# TOP.net
KiCad netlist of a schematic drawn in Altium Designer
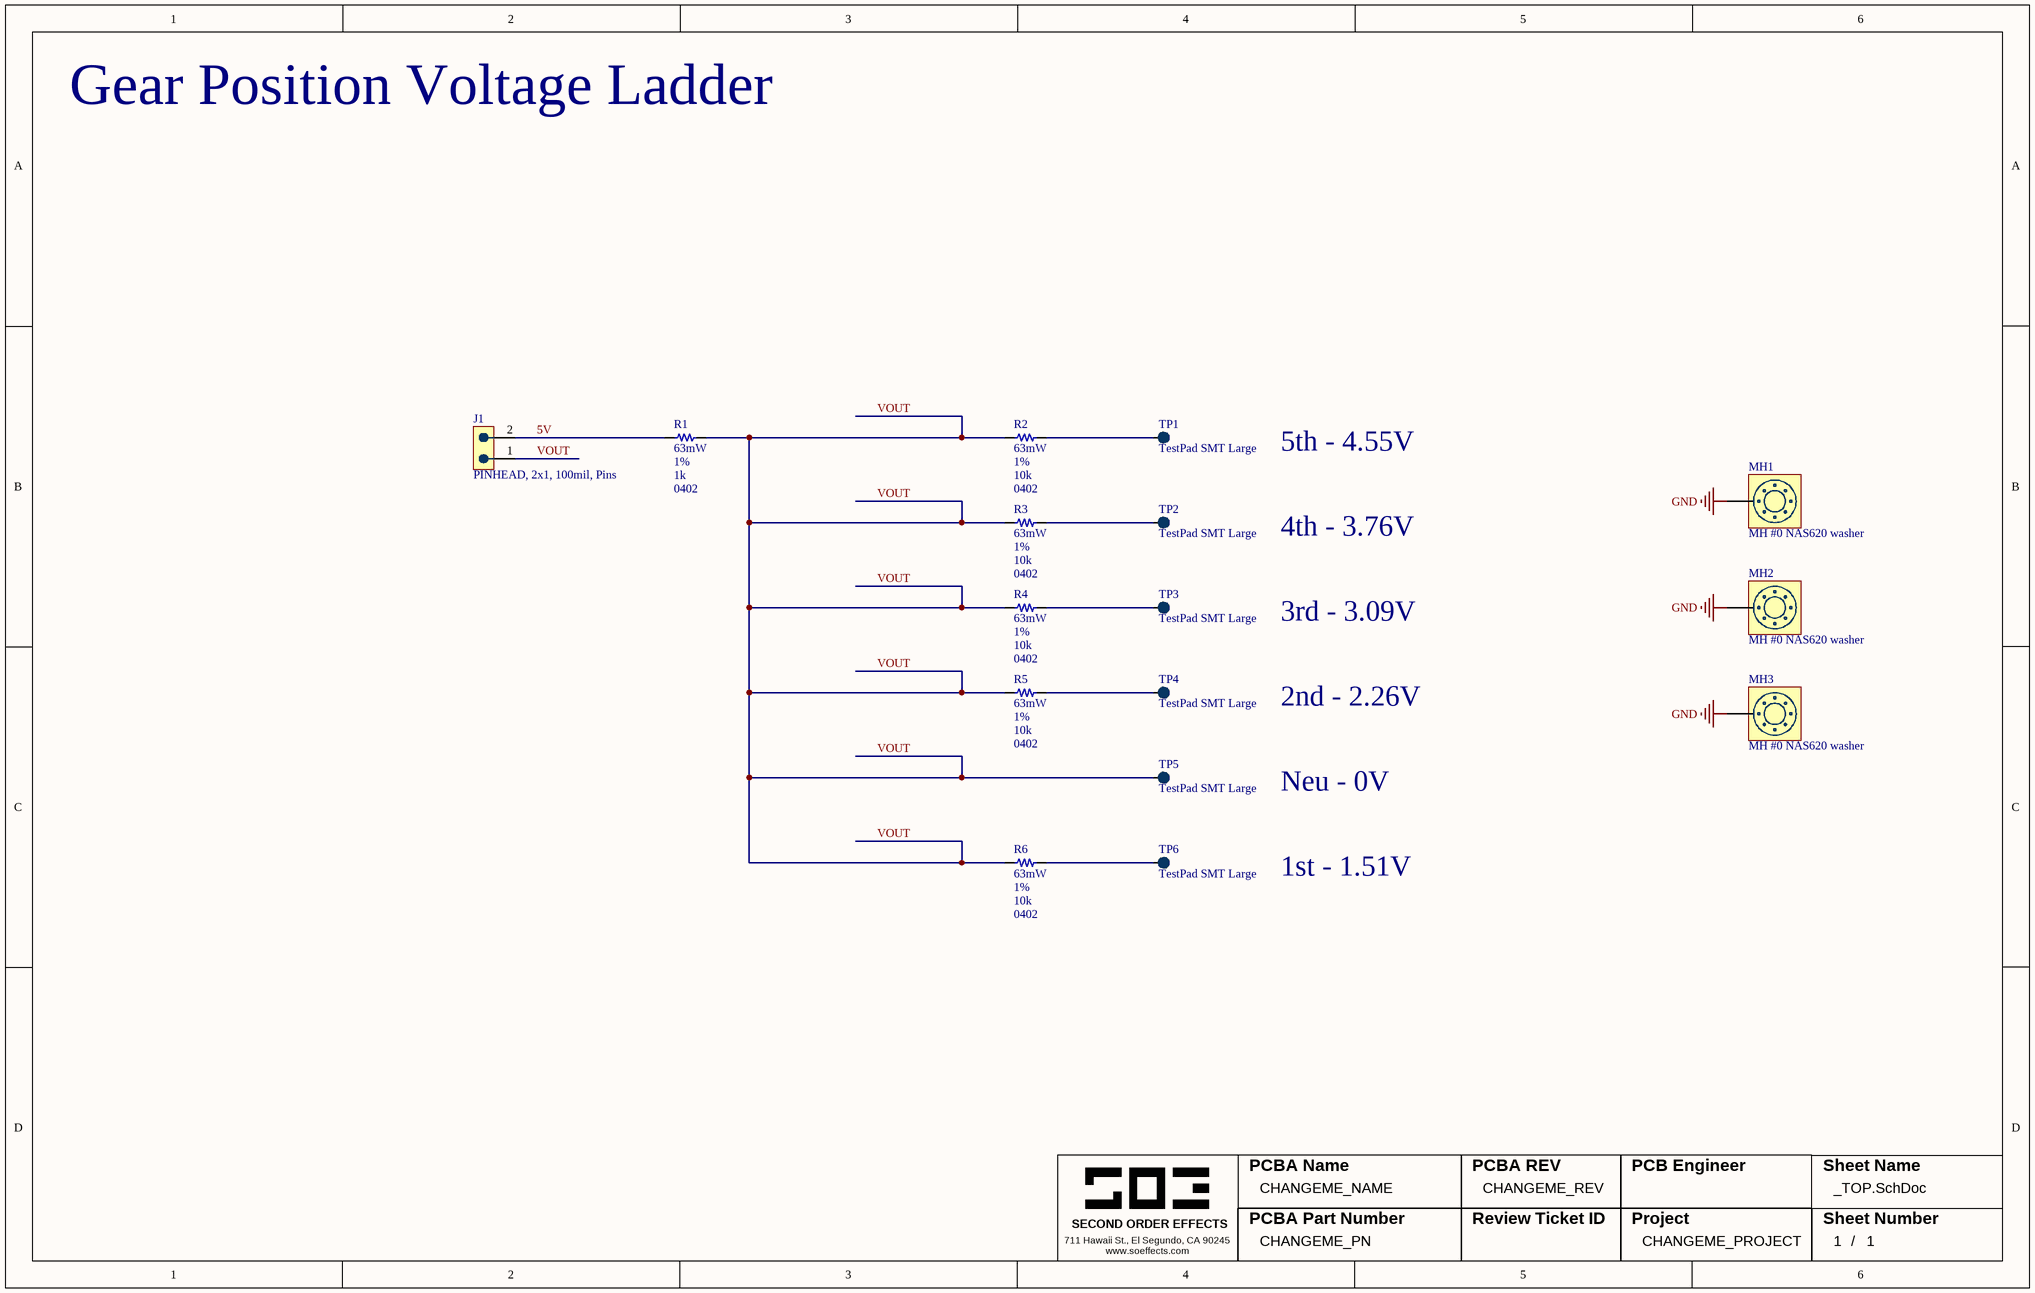
[diagram p0: _TOP.SchDoc]

(export (version "E")
  (design (tool "Eeschema 10.0.6"))
  (components
    (comp (ref "J1")
      (value "PINHEAD, 2x1, 100mil, Pins")
      (footprint "PINHEAD 2 x 1 100MIL PIN")
      (description "Headers & Wire Housings 2.54MM CGRIDIII HDR 2P VERT SR SEL AU")
      (libsource (lib "SOE Vault") (part "PINHEAD 2x1 PINS"))
    )
    (comp (ref "MH1")
      (value "MH #0 NAS620 washer")
      (footprint "MH_0_NAS620")
      (libsource (lib "SOE Vault") (part "MountingHole-4mm"))
    )
    (comp (ref "MH2")
      (value "MH #0 NAS620 washer")
      (footprint "MH_0_NAS620")
      (libsource (lib "SOE Vault") (part "MountingHole-4mm"))
    )
    (comp (ref "MH3")
      (value "MH #0 NAS620 washer")
      (footprint "MH_0_NAS620")
      (libsource (lib "SOE Vault") (part "MountingHole-4mm"))
    )
    (comp (ref "R1")
      (value "R 0402 1.00k 1% 0.063W ±100PPM/°C 50V AEC-Q200")
      (footprint "R_0402")
      (description "SMD Resistor, Thick Film, Automotive")
      (fields
        (field (name "POWER RATING") "63mW")
        (field (name "TOLERANCE") "1%")
        (field (name "RESISTANCE") "1k")
        (field (name "CASE/PACKAGE") "0402")
      )
      (libsource (lib "SOE Vault") (part "r4"))
    )
    (comp (ref "R2")
      (value "R 0402 10.0k 1% 0.063W ±100PPM/°C 50V AEC-Q200")
      (footprint "R_0402")
      (description "SMD Resistor, Thick Film, Automotive")
      (fields
        (field (name "POWER RATING") "63mW")
        (field (name "TOLERANCE") "1%")
        (field (name "RESISTANCE") "10k")
        (field (name "CASE/PACKAGE") "0402")
      )
      (libsource (lib "SOE Vault") (part "r4"))
    )
    (comp (ref "R3")
      (value "R 0402 10.0k 1% 0.063W ±100PPM/°C 50V AEC-Q200")
      (footprint "R_0402")
      (description "SMD Resistor, Thick Film, Automotive")
      (fields
        (field (name "POWER RATING") "63mW")
        (field (name "TOLERANCE") "1%")
        (field (name "RESISTANCE") "10k")
        (field (name "CASE/PACKAGE") "0402")
      )
      (libsource (lib "SOE Vault") (part "r4"))
    )
    (comp (ref "R4")
      (value "R 0402 10.0k 1% 0.063W ±100PPM/°C 50V AEC-Q200")
      (footprint "R_0402")
      (description "SMD Resistor, Thick Film, Automotive")
      (fields
        (field (name "POWER RATING") "63mW")
        (field (name "TOLERANCE") "1%")
        (field (name "RESISTANCE") "10k")
        (field (name "CASE/PACKAGE") "0402")
      )
      (libsource (lib "SOE Vault") (part "r4"))
    )
    (comp (ref "R5")
      (value "R 0402 10.0k 1% 0.063W ±100PPM/°C 50V AEC-Q200")
      (footprint "R_0402")
      (description "SMD Resistor, Thick Film, Automotive")
      (fields
        (field (name "POWER RATING") "63mW")
        (field (name "TOLERANCE") "1%")
        (field (name "RESISTANCE") "10k")
        (field (name "CASE/PACKAGE") "0402")
      )
      (libsource (lib "SOE Vault") (part "r4"))
    )
    (comp (ref "R6")
      (value "R 0402 10.0k 1% 0.063W ±100PPM/°C 50V AEC-Q200")
      (footprint "R_0402")
      (description "SMD Resistor, Thick Film, Automotive")
      (fields
        (field (name "POWER RATING") "63mW")
        (field (name "TOLERANCE") "1%")
        (field (name "RESISTANCE") "10k")
        (field (name "CASE/PACKAGE") "0402")
      )
      (libsource (lib "SOE Vault") (part "r4"))
    )
    (comp (ref "TP1")
      (value "TestPad SMT Large")
      (footprint "TEST_POINT_SMD_LARGE")
      (description "Test pad 2mm")
      (libsource (lib "SOE Vault") (part "TestPad"))
    )
    (comp (ref "TP2")
      (value "TestPad SMT Large")
      (footprint "TEST_POINT_SMD_LARGE")
      (description "Test pad 2mm")
      (libsource (lib "SOE Vault") (part "TestPad"))
    )
    (comp (ref "TP3")
      (value "TestPad SMT Large")
      (footprint "TEST_POINT_SMD_LARGE")
      (description "Test pad 2mm")
      (libsource (lib "SOE Vault") (part "TestPad"))
    )
    (comp (ref "TP4")
      (value "TestPad SMT Large")
      (footprint "TEST_POINT_SMD_LARGE")
      (description "Test pad 2mm")
      (libsource (lib "SOE Vault") (part "TestPad"))
    )
    (comp (ref "TP5")
      (value "TestPad SMT Large")
      (footprint "TEST_POINT_SMD_LARGE")
      (description "Test pad 2mm")
      (libsource (lib "SOE Vault") (part "TestPad"))
    )
    (comp (ref "TP6")
      (value "TestPad SMT Large")
      (footprint "TEST_POINT_SMD_LARGE")
      (description "Test pad 2mm")
      (libsource (lib "SOE Vault") (part "TestPad"))
    )
  )
  (nets
    (net (code "1") (name "/5V") (class "Default")
      (node (ref "J1") (pin "2") (pinfunction "2_2") (pintype "passive"))
      (node (ref "R1") (pin "2") (pinfunction "2_2") (pintype "passive"))
    )
    (net (code "2") (name "/VOUT") (class "Default")
      (node (ref "J1") (pin "1") (pinfunction "1_1") (pintype "passive"))
      (node (ref "R1") (pin "1") (pinfunction "1_1") (pintype "passive"))
      (node (ref "R2") (pin "2") (pinfunction "2_2") (pintype "passive"))
      (node (ref "R3") (pin "2") (pinfunction "2_2") (pintype "passive"))
      (node (ref "R4") (pin "2") (pinfunction "2_2") (pintype "passive"))
      (node (ref "R5") (pin "2") (pinfunction "2_2") (pintype "passive"))
      (node (ref "R6") (pin "2") (pinfunction "2_2") (pintype "passive"))
      (node (ref "TP5") (pin "1") (pinfunction "TP_1") (pintype "passive"))
    )
    (net (code "3") (name "GND") (class "Default")
      (node (ref "MH1") (pin "1") (pinfunction "MH_1") (pintype "passive"))
      (node (ref "MH2") (pin "1") (pinfunction "MH_1") (pintype "passive"))
      (node (ref "MH3") (pin "1") (pinfunction "MH_1") (pintype "passive"))
    )
    (net (code "4") (name "Net-(TP1-TP)") (class "Default")
      (node (ref "R2") (pin "1") (pinfunction "1_1") (pintype "passive"))
      (node (ref "TP1") (pin "1") (pinfunction "TP_1") (pintype "passive"))
    )
    (net (code "5") (name "Net-(TP2-TP)") (class "Default")
      (node (ref "R3") (pin "1") (pinfunction "1_1") (pintype "passive"))
      (node (ref "TP2") (pin "1") (pinfunction "TP_1") (pintype "passive"))
    )
    (net (code "6") (name "Net-(TP3-TP)") (class "Default")
      (node (ref "R4") (pin "1") (pinfunction "1_1") (pintype "passive"))
      (node (ref "TP3") (pin "1") (pinfunction "TP_1") (pintype "passive"))
    )
    (net (code "7") (name "Net-(TP4-TP)") (class "Default")
      (node (ref "R5") (pin "1") (pinfunction "1_1") (pintype "passive"))
      (node (ref "TP4") (pin "1") (pinfunction "TP_1") (pintype "passive"))
    )
    (net (code "8") (name "Net-(TP6-TP)") (class "Default")
      (node (ref "R6") (pin "1") (pinfunction "1_1") (pintype "passive"))
      (node (ref "TP6") (pin "1") (pinfunction "TP_1") (pintype "passive"))
    )
  )
)
